# vbus_v2.net
KiCad netlist of a schematic drawn in EAGLE
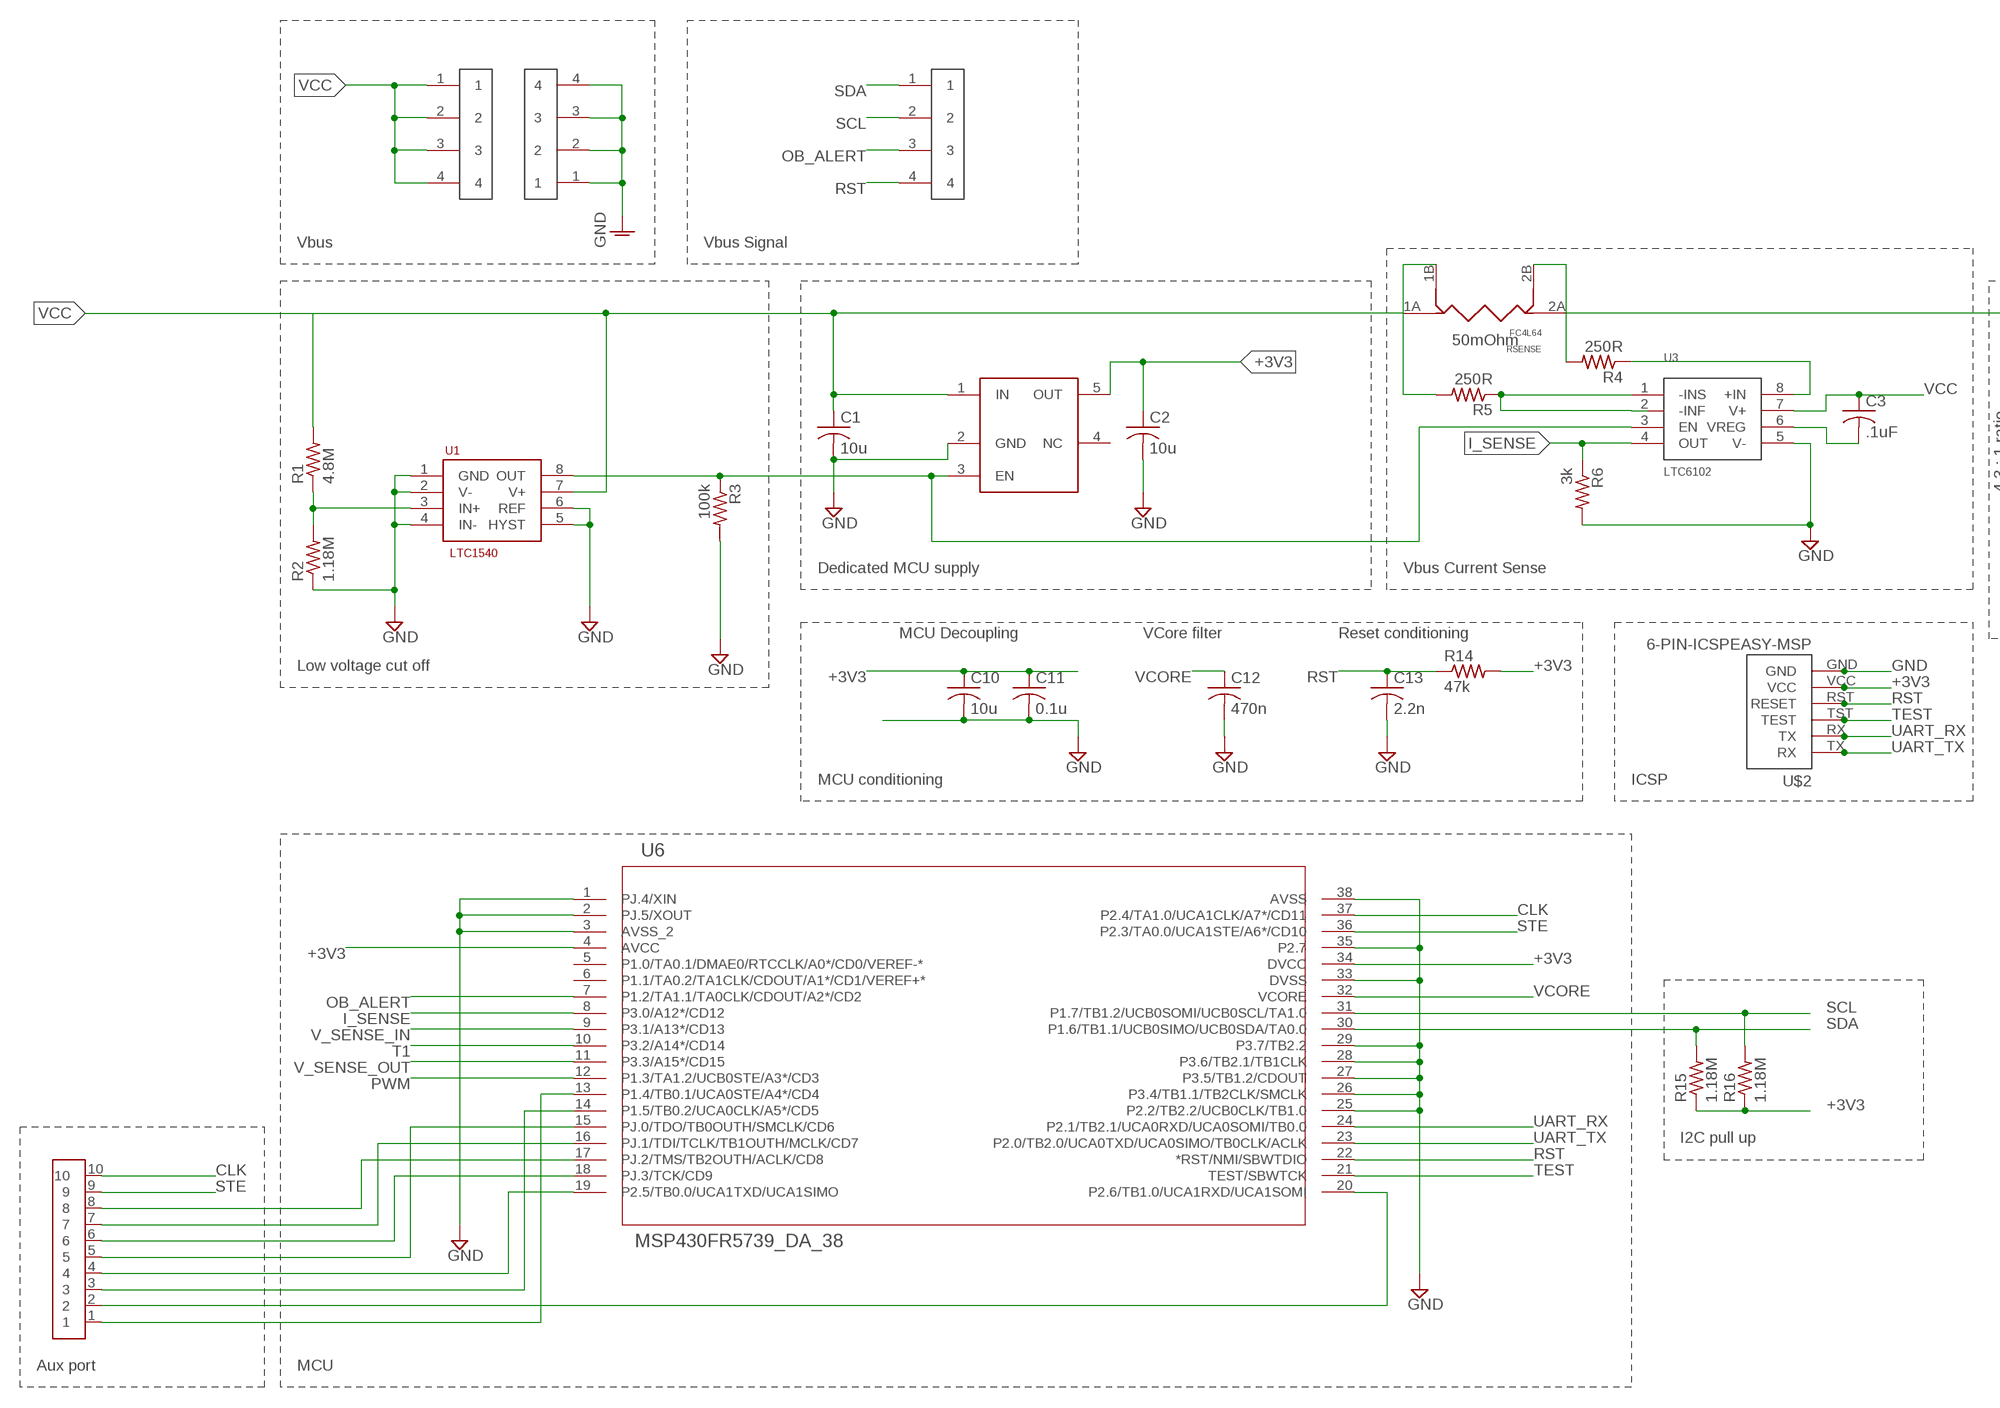
[diagram p0: schematic, sheet 1, part 1 of 2]
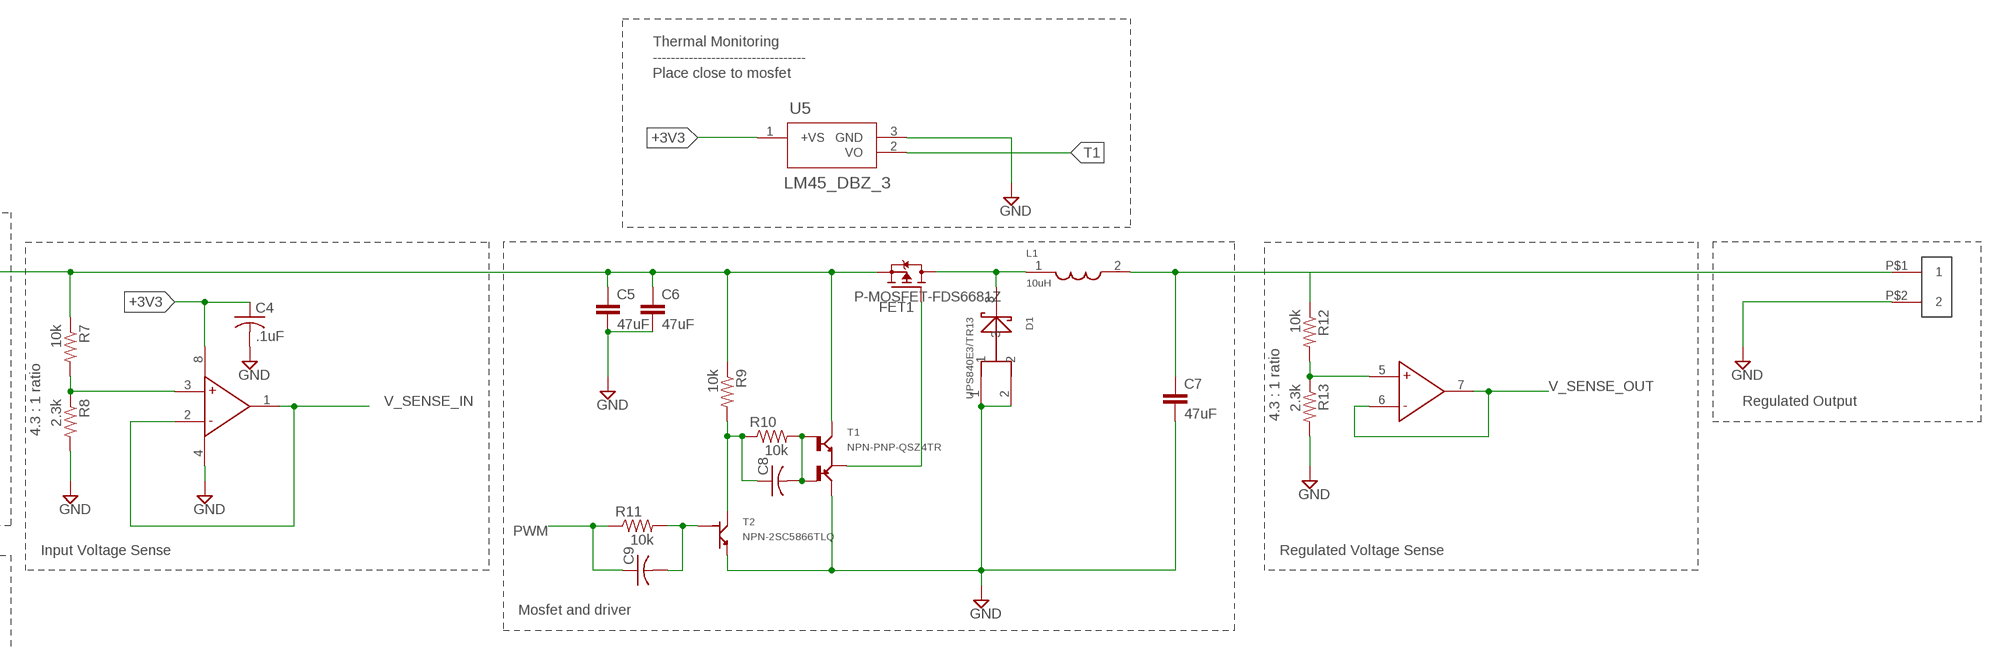
[diagram p1: schematic, sheet 1, part 2 of 2]

(export (version "E")
  (design (tool "Eeschema 10.0.6"))
  (components
    (comp (ref "C1")
      (value "10u")
      (footprint "eagle-import:C1206")
      (libsource (lib "eagle-import") (part "C-USC1206"))
    )
    (comp (ref "C2")
      (value "10u")
      (footprint "eagle-import:C1206")
      (libsource (lib "eagle-import") (part "C-USC1206"))
    )
    (comp (ref "C3")
      (value ".1uF")
      (footprint "eagle-import:C0805")
      (libsource (lib "eagle-import") (part "C-USC0805"))
    )
    (comp (ref "C4")
      (value ".1uF")
      (footprint "eagle-import:C0805")
      (libsource (lib "eagle-import") (part "C-USC0805"))
    )
    (comp (ref "C5")
      (value "47uF")
      (footprint "eagle-import:C1206")
      (libsource (lib "eagle-import") (part "C-EUC1206"))
    )
    (comp (ref "C6")
      (value "47uF")
      (footprint "eagle-import:C1206")
      (libsource (lib "eagle-import") (part "C-EUC1206"))
    )
    (comp (ref "C7")
      (value "47uF")
      (footprint "eagle-import:C1206")
      (libsource (lib "eagle-import") (part "C-EUC1206"))
    )
    (comp (ref "C8")
      (value "C-USC0805")
      (footprint "eagle-import:C0805")
      (libsource (lib "eagle-import") (part "C-USC0805"))
    )
    (comp (ref "C9")
      (value "C-USC0805")
      (footprint "eagle-import:C0805")
      (libsource (lib "eagle-import") (part "C-USC0805"))
    )
    (comp (ref "C10")
      (value "10u")
      (footprint "eagle-import:C1206")
      (libsource (lib "eagle-import") (part "C-USC1206"))
    )
    (comp (ref "C11")
      (value "0.1u")
      (footprint "eagle-import:C1206")
      (libsource (lib "eagle-import") (part "C-USC1206"))
    )
    (comp (ref "C12")
      (value "470n")
      (footprint "eagle-import:C1206")
      (libsource (lib "eagle-import") (part "C-USC1206"))
    )
    (comp (ref "C13")
      (value "2.2n")
      (footprint "eagle-import:C1206")
      (libsource (lib "eagle-import") (part "C-USC1206"))
    )
    (comp (ref "D1")
      (value "UPS840E3/TR13")
      (footprint "eagle-import:UPS840E3")
      (libsource (lib "eagle-import") (part "UPS840E3"))
    )
    (comp (ref "FET1")
      (value "P-MOSFET-FDS6681Z")
      (footprint "eagle-import:SOIC-8")
      (libsource (lib "eagle-import") (part "P-MOSFET-FDS6681Z"))
    )
    (comp (ref "L1")
      (value "10uH")
      (footprint "eagle-import:HCF1007")
      (libsource (lib "eagle-import") (part "HCF1007"))
    )
    (comp (ref "R1")
      (value "4.8M")
      (footprint "eagle-import:R1206")
      (libsource (lib "eagle-import") (part "R-US_R1206"))
    )
    (comp (ref "R2")
      (value "1.18M")
      (footprint "eagle-import:R1206")
      (libsource (lib "eagle-import") (part "R-US_R1206"))
    )
    (comp (ref "R3")
      (value "100k")
      (footprint "eagle-import:R1206")
      (libsource (lib "eagle-import") (part "R-US_R1206"))
    )
    (comp (ref "R4")
      (value "250R")
      (footprint "eagle-import:M0805")
      (libsource (lib "eagle-import") (part "R-US_M0805"))
    )
    (comp (ref "R5")
      (value "250R")
      (footprint "eagle-import:M0805")
      (libsource (lib "eagle-import") (part "R-US_M0805"))
    )
    (comp (ref "R6")
      (value "3k")
      (footprint "eagle-import:M0805")
      (libsource (lib "eagle-import") (part "R-US_M0805"))
    )
    (comp (ref "R7")
      (value "10k")
      (footprint "eagle-import:M0805")
      (libsource (lib "eagle-import") (part "R-US_M0805"))
    )
    (comp (ref "R8")
      (value "2.3k")
      (footprint "eagle-import:M0805")
      (libsource (lib "eagle-import") (part "R-US_M0805"))
    )
    (comp (ref "R9")
      (value "10k")
      (footprint "eagle-import:M0805")
      (libsource (lib "eagle-import") (part "R-US_M0805"))
    )
    (comp (ref "R10")
      (value "10k")
      (footprint "eagle-import:M0805")
      (libsource (lib "eagle-import") (part "R-US_M0805"))
    )
    (comp (ref "R11")
      (value "10k")
      (footprint "eagle-import:M0805")
      (libsource (lib "eagle-import") (part "R-US_M0805"))
    )
    (comp (ref "R12")
      (value "10k")
      (footprint "eagle-import:M0805")
      (libsource (lib "eagle-import") (part "R-US_M0805"))
    )
    (comp (ref "R13")
      (value "2.3k")
      (footprint "eagle-import:M0805")
      (libsource (lib "eagle-import") (part "R-US_M0805"))
    )
    (comp (ref "R14")
      (value "47k")
      (footprint "eagle-import:R1206")
      (libsource (lib "eagle-import") (part "R-US_R1206"))
    )
    (comp (ref "R15")
      (value "1.18M")
      (footprint "eagle-import:R0805")
      (libsource (lib "eagle-import") (part "R-US_R0805"))
    )
    (comp (ref "R16")
      (value "1.18M")
      (footprint "eagle-import:R0805")
      (libsource (lib "eagle-import") (part "R-US_R0805"))
    )
    (comp (ref "RSENSE")
      (value "FC4L64")
      (footprint "eagle-import:FC4L64")
      (libsource (lib "eagle-import") (part "FC4L64"))
    )
    (comp (ref "T1")
      (value "NPN-PNP-QSZ4TR")
      (footprint "eagle-import:TSMT5")
      (libsource (lib "eagle-import") (part "NPN-PNP-QSZ4TR"))
    )
    (comp (ref "T2")
      (value "NPN-2SC5866TLQ")
      (footprint "eagle-import:TSMT3")
      (libsource (lib "eagle-import") (part "NPN-2SC5866TLQ"))
    )
    (comp (ref "U$1")
      (value "MICROPITCH")
      (footprint "eagle-import:2X5-1.27MM")
      (libsource (lib "eagle-import") (part "MICROPITCH"))
    )
    (comp (ref "U$2")
      (value "6-PIN-ICSPEASY-MSP")
      (footprint "eagle-import:EASYMSP-6PIN")
      (libsource (lib "eagle-import") (part "6-PIN-ICSPEASY-MSP"))
    )
    (comp (ref "U$3")
      (value "1X4_HEADER")
      (footprint "eagle-import:1X4-.1HEADER")
      (libsource (lib "eagle-import") (part "1X4_HEADER"))
    )
    (comp (ref "U$5")
      (value "MOLEX-0436500200")
      (footprint "eagle-import:MOLEX_MICROFIT-2")
      (libsource (lib "eagle-import") (part "MOLEX-0436500200"))
    )
    (comp (ref "U$8")
      (value "1X4_HEADER")
      (footprint "eagle-import:1X4-.1HEADER")
      (libsource (lib "eagle-import") (part "1X4_HEADER"))
    )
    (comp (ref "U$11")
      (value "1X4_HEADER")
      (footprint "eagle-import:1X4-.1HEADER")
      (libsource (lib "eagle-import") (part "1X4_HEADER"))
    )
    (comp (ref "U1")
      (value "LTC1540")
      (footprint "eagle-import:S8")
      (libsource (lib "eagle-import") (part "LTC1540"))
    )
    (comp (ref "U2")
      (value "TPS70930-Q1")
      (footprint "eagle-import:SOT-23")
      (libsource (lib "eagle-import") (part "TPS70930-Q1"))
    )
    (comp (ref "U3")
      (value "LTC6102")
      (footprint "eagle-import:MS8")
      (libsource (lib "eagle-import") (part "LTC6102"))
    )
    (comp (ref "U4")
      (value "LMP2202")
      (footprint "eagle-import:D8-L")
      (libsource (lib "eagle-import") (part "LMP2202"))
    )
    (comp (ref "U5")
      (value "LM45_DBZ_3")
      (footprint "eagle-import:MF03A")
      (fields (field (name "PARTNUMBER") "LM45BIM3"))
      (libsource (lib "eagle-import") (part "LM45_DBZ_3"))
    )
    (comp (ref "U6")
      (value "MSP430FR5739_DA_38")
      (footprint "eagle-import:DA38")
      (fields
        (field (name "GENERIC_PART_NUMBER") "MSP430FR5739")
        (field (name "MANUFACTURER") "Texas Instruments")
        (field (name "MANUFACTURER_PART_NUMBER") "msp430fr5739_da_38")
      )
      (libsource (lib "eagle-import") (part "MSP430FR5739_DA_38"))
    )
  )
  (nets
    (net (code "1") (name "+3V3") (class "Default")
      (node (ref "C10") (pin "1") (pinfunction "1_1") (pintype "passive"))
      (node (ref "C11") (pin "1") (pinfunction "1_1") (pintype "passive"))
      (node (ref "C2") (pin "1") (pinfunction "1_1") (pintype "passive"))
      (node (ref "C4") (pin "1") (pinfunction "1_1") (pintype "passive"))
      (node (ref "R14") (pin "2") (pinfunction "2_2") (pintype "passive"))
      (node (ref "R15") (pin "1") (pinfunction "1_1") (pintype "passive"))
      (node (ref "R16") (pin "1") (pinfunction "1_1") (pintype "passive"))
      (node (ref "U$2") (pin "VCC") (pinfunction "VCC_VCC") (pintype "bidirectional"))
      (node (ref "U2") (pin "5") (pinfunction "OUT_5") (pintype "bidirectional"))
      (node (ref "U4") (pin "8") (pinfunction "VIN_8") (pintype "bidirectional"))
      (node (ref "U5") (pin "1") (pinfunction "+VS_1") (pintype "input"))
      (node (ref "U6") (pin "34") (pinfunction "DVCC_34") (pintype "power_in"))
      (node (ref "U6") (pin "4") (pinfunction "AVCC_4") (pintype "power_in"))
    )
    (net (code "2") (name "/CLK") (class "Default")
      (node (ref "U$1") (pin "10") (pinfunction "10_10") (pintype "bidirectional"))
      (node (ref "U6") (pin "37") (pinfunction "P2.4/TA1.0/UCA1CLK/A7*/CD11_37") (pintype "bidirectional"))
    )
    (net (code "3") (name "/OB_ALERT") (class "Default")
      (node (ref "U$8") (pin "3") (pinfunction "3_3") (pintype "bidirectional"))
      (node (ref "U6") (pin "7") (pinfunction "P1.2/TA1.1/TA0CLK/CDOUT/A2*/CD2_7") (pintype "bidirectional"))
    )
    (net (code "4") (name "/PWM") (class "Default")
      (node (ref "C9") (pin "1") (pinfunction "1_1") (pintype "passive"))
      (node (ref "R11") (pin "1") (pinfunction "1_1") (pintype "passive"))
      (node (ref "U6") (pin "12") (pinfunction "P1.3/TA1.2/UCB0STE/A3*/CD3_12") (pintype "bidirectional"))
    )
    (net (code "5") (name "/RST") (class "Default")
      (node (ref "C13") (pin "1") (pinfunction "1_1") (pintype "passive"))
      (node (ref "R14") (pin "1") (pinfunction "1_1") (pintype "passive"))
      (node (ref "U$2") (pin "RST") (pinfunction "RESET_RST") (pintype "bidirectional"))
      (node (ref "U$8") (pin "4") (pinfunction "4_4") (pintype "bidirectional"))
      (node (ref "U6") (pin "22") (pinfunction "*RST/NMI/SBWTDIO_22") (pintype "bidirectional"))
    )
    (net (code "6") (name "/SCL") (class "Default")
      (node (ref "R16") (pin "2") (pinfunction "2_2") (pintype "passive"))
      (node (ref "U$8") (pin "2") (pinfunction "2_2") (pintype "bidirectional"))
      (node (ref "U6") (pin "31") (pinfunction "P1.7/TB1.2/UCB0SOMI/UCB0SCL/TA1.0_31") (pintype "bidirectional"))
    )
    (net (code "7") (name "/SDA") (class "Default")
      (node (ref "R15") (pin "2") (pinfunction "2_2") (pintype "passive"))
      (node (ref "U$8") (pin "1") (pinfunction "1_1") (pintype "bidirectional"))
      (node (ref "U6") (pin "30") (pinfunction "P1.6/TB1.1/UCB0SIMO/UCB0SDA/TA0.0_30") (pintype "bidirectional"))
    )
    (net (code "8") (name "/STE") (class "Default")
      (node (ref "U$1") (pin "9") (pinfunction "9_9") (pintype "bidirectional"))
      (node (ref "U6") (pin "36") (pinfunction "P2.3/TA0.0/UCA1STE/A6*/CD10_36") (pintype "bidirectional"))
    )
    (net (code "9") (name "/TEST") (class "Default")
      (node (ref "U$2") (pin "TST") (pinfunction "TEST_TST") (pintype "bidirectional"))
      (node (ref "U6") (pin "21") (pinfunction "TEST/SBWTCK_21") (pintype "bidirectional"))
    )
    (net (code "10") (name "/UART_RX") (class "Default")
      (node (ref "U$2") (pin "RX") (pinfunction "TX_RX") (pintype "bidirectional"))
      (node (ref "U6") (pin "24") (pinfunction "P2.1/TB2.1/UCA0RXD/UCA0SOMI/TB0.0_24") (pintype "bidirectional"))
    )
    (net (code "11") (name "/UART_TX") (class "Default")
      (node (ref "U$2") (pin "TX") (pinfunction "RX_TX") (pintype "bidirectional"))
      (node (ref "U6") (pin "23") (pinfunction "P2.0/TB2.0/UCA0TXD/UCA0SIMO/TB0CLK/ACLK_23") (pintype "bidirectional"))
    )
    (net (code "12") (name "/VCORE") (class "Default")
      (node (ref "C12") (pin "1") (pinfunction "1_1") (pintype "passive"))
      (node (ref "U6") (pin "32") (pinfunction "VCORE_32") (pintype "power_in"))
    )
    (net (code "13") (name "/V_SENSE_IN") (class "Default")
      (node (ref "U4") (pin "1") (pinfunction "OUT_1") (pintype "bidirectional"))
      (node (ref "U4") (pin "2") (pinfunction "-_2") (pintype "bidirectional"))
      (node (ref "U6") (pin "9") (pinfunction "P3.1/A13*/CD13_9") (pintype "bidirectional"))
    )
    (net (code "14") (name "/V_SENSE_OUT") (class "Default")
      (node (ref "U4") (pin "6") (pinfunction "-_6") (pintype "bidirectional"))
      (node (ref "U4") (pin "7") (pinfunction "OUT_7") (pintype "bidirectional"))
      (node (ref "U6") (pin "11") (pinfunction "P3.3/A15*/CD15_11") (pintype "bidirectional"))
    )
    (net (code "15") (name "GND") (class "Default")
      (node (ref "C1") (pin "2") (pinfunction "2_2") (pintype "passive"))
      (node (ref "C10") (pin "2") (pinfunction "2_2") (pintype "passive"))
      (node (ref "C11") (pin "2") (pinfunction "2_2") (pintype "passive"))
      (node (ref "C12") (pin "2") (pinfunction "2_2") (pintype "passive"))
      (node (ref "C13") (pin "2") (pinfunction "2_2") (pintype "passive"))
      (node (ref "C2") (pin "2") (pinfunction "2_2") (pintype "passive"))
      (node (ref "C4") (pin "2") (pinfunction "2_2") (pintype "passive"))
      (node (ref "C5") (pin "2") (pinfunction "2_2") (pintype "passive"))
      (node (ref "C6") (pin "2") (pinfunction "2_2") (pintype "passive"))
      (node (ref "C7") (pin "2") (pinfunction "2_2") (pintype "passive"))
      (node (ref "D1") (pin "1") (pinfunction "1_1") (pintype "bidirectional"))
      (node (ref "D1") (pin "2") (pinfunction "2_2") (pintype "bidirectional"))
      (node (ref "R13") (pin "2") (pinfunction "2_2") (pintype "passive"))
      (node (ref "R2") (pin "1") (pinfunction "1_1") (pintype "passive"))
      (node (ref "R3") (pin "2") (pinfunction "2_2") (pintype "passive"))
      (node (ref "R6") (pin "2") (pinfunction "2_2") (pintype "passive"))
      (node (ref "R8") (pin "2") (pinfunction "2_2") (pintype "passive"))
      (node (ref "T1") (pin "5") (pinfunction "E_5") (pintype "bidirectional"))
      (node (ref "T2") (pin "2") (pinfunction "E_2") (pintype "bidirectional"))
      (node (ref "U$2") (pin "GND") (pinfunction "GND_GND") (pintype "bidirectional"))
      (node (ref "U$3") (pin "1") (pinfunction "1_1") (pintype "bidirectional"))
      (node (ref "U$3") (pin "2") (pinfunction "2_2") (pintype "bidirectional"))
      (node (ref "U$3") (pin "3") (pinfunction "3_3") (pintype "bidirectional"))
      (node (ref "U$3") (pin "4") (pinfunction "4_4") (pintype "bidirectional"))
      (node (ref "U$5") (pin "P$2") (pinfunction "2_P$2") (pintype "bidirectional"))
      (node (ref "U1") (pin "1") (pinfunction "GND_1") (pintype "bidirectional"))
      (node (ref "U1") (pin "2") (pinfunction "V-_2") (pintype "bidirectional"))
      (node (ref "U1") (pin "4") (pinfunction "IN-_4") (pintype "bidirectional"))
      (node (ref "U1") (pin "5") (pinfunction "HYST_5") (pintype "bidirectional"))
      (node (ref "U1") (pin "6") (pinfunction "REF_6") (pintype "bidirectional"))
      (node (ref "U2") (pin "2") (pinfunction "GND_2") (pintype "bidirectional"))
      (node (ref "U3") (pin "5") (pinfunction "V-_5") (pintype "power_in"))
      (node (ref "U4") (pin "4") (pinfunction "GND_4") (pintype "bidirectional"))
      (node (ref "U5") (pin "3") (pinfunction "GND_3") (pintype "passive"))
      (node (ref "U6") (pin "1") (pinfunction "PJ.4/XIN_1") (pintype "bidirectional"))
      (node (ref "U6") (pin "2") (pinfunction "PJ.5/XOUT_2") (pintype "bidirectional"))
      (node (ref "U6") (pin "25") (pinfunction "P2.2/TB2.2/UCB0CLK/TB1.0_25") (pintype "bidirectional"))
      (node (ref "U6") (pin "26") (pinfunction "P3.4/TB1.1/TB2CLK/SMCLK_26") (pintype "bidirectional"))
      (node (ref "U6") (pin "27") (pinfunction "P3.5/TB1.2/CDOUT_27") (pintype "bidirectional"))
      (node (ref "U6") (pin "28") (pinfunction "P3.6/TB2.1/TB1CLK_28") (pintype "bidirectional"))
      (node (ref "U6") (pin "29") (pinfunction "P3.7/TB2.2_29") (pintype "bidirectional"))
      (node (ref "U6") (pin "3") (pinfunction "AVSS_2_3") (pintype "power_in"))
      (node (ref "U6") (pin "33") (pinfunction "DVSS_33") (pintype "power_in"))
      (node (ref "U6") (pin "35") (pinfunction "P2.7_35") (pintype "bidirectional"))
      (node (ref "U6") (pin "38") (pinfunction "AVSS_38") (pintype "power_in"))
    )
    (net (code "16") (name "I_SENSE") (class "Default")
      (node (ref "R6") (pin "1") (pinfunction "1_1") (pintype "passive"))
      (node (ref "U3") (pin "4") (pinfunction "OUT_4") (pintype "power_in"))
      (node (ref "U6") (pin "8") (pinfunction "P3.0/A12*/CD12_8") (pintype "bidirectional"))
    )
    (net (code "17") (name "Net-(FET1-G)") (class "Default")
      (node (ref "FET1") (pin "4") (pinfunction "G_4") (pintype "passive"))
      (node (ref "T1") (pin "2") (pinfunction "G_2") (pintype "bidirectional"))
    )
    (net (code "18") (name "Net-(L1-A)") (class "Default")
      (node (ref "D1") (pin "3") (pinfunction "3_3") (pintype "bidirectional"))
      (node (ref "FET1") (pin "1") (pinfunction "S_1") (pintype "passive"))
      (node (ref "FET1") (pin "2") (pinfunction "S_2") (pintype "passive"))
      (node (ref "FET1") (pin "3") (pinfunction "S_3") (pintype "passive"))
      (node (ref "L1") (pin "1") (pinfunction "A_1") (pintype "bidirectional"))
    )
    (net (code "19") (name "Net-(L1-B)") (class "Default")
      (node (ref "C7") (pin "1") (pinfunction "1_1") (pintype "passive"))
      (node (ref "L1") (pin "2") (pinfunction "B_2") (pintype "bidirectional"))
      (node (ref "R12") (pin "1") (pinfunction "1_1") (pintype "passive"))
      (node (ref "U$5") (pin "P$1") (pinfunction "1_P$1") (pintype "bidirectional"))
    )
    (net (code "20") (name "Net-(RSENSE-1A)") (class "Default")
      (node (ref "C5") (pin "1") (pinfunction "1_1") (pintype "passive"))
      (node (ref "C6") (pin "1") (pinfunction "1_1") (pintype "passive"))
      (node (ref "FET1") (pin "5") (pinfunction "D_5") (pintype "passive"))
      (node (ref "FET1") (pin "6") (pinfunction "D_6") (pintype "passive"))
      (node (ref "FET1") (pin "7") (pinfunction "D_7") (pintype "passive"))
      (node (ref "FET1") (pin "8") (pinfunction "D_8") (pintype "passive"))
      (node (ref "R7") (pin "1") (pinfunction "1_1") (pintype "passive"))
      (node (ref "R9") (pin "1") (pinfunction "1_1") (pintype "passive"))
      (node (ref "RSENSE") (pin "2A") (pinfunction "1A_2A") (pintype "bidirectional"))
      (node (ref "T1") (pin "4") (pinfunction "C_4") (pintype "bidirectional"))
    )
    (net (code "21") (name "Net-(RSENSE-1B)") (class "Default")
      (node (ref "R4") (pin "2") (pinfunction "2_2") (pintype "passive"))
      (node (ref "RSENSE") (pin "2B") (pinfunction "1B_2B") (pintype "bidirectional"))
    )
    (net (code "22") (name "Net-(RSENSE-2B)") (class "Default")
      (node (ref "R5") (pin "2") (pinfunction "2_2") (pintype "passive"))
      (node (ref "RSENSE") (pin "1B") (pinfunction "2B_1B") (pintype "bidirectional"))
    )
    (net (code "23") (name "Net-(T1-G1)") (class "Default")
      (node (ref "C8") (pin "2") (pinfunction "2_2") (pintype "passive"))
      (node (ref "R10") (pin "2") (pinfunction "2_2") (pintype "passive"))
      (node (ref "T1") (pin "1") (pinfunction "G2_1") (pintype "bidirectional"))
      (node (ref "T1") (pin "3") (pinfunction "G1_3") (pintype "bidirectional"))
    )
    (net (code "24") (name "Net-(T2-B)") (class "Default")
      (node (ref "C9") (pin "2") (pinfunction "2_2") (pintype "passive"))
      (node (ref "R11") (pin "2") (pinfunction "2_2") (pintype "passive"))
      (node (ref "T2") (pin "1") (pinfunction "B_1") (pintype "bidirectional"))
    )
    (net (code "25") (name "Net-(T2-C)") (class "Default")
      (node (ref "C8") (pin "1") (pinfunction "1_1") (pintype "passive"))
      (node (ref "R10") (pin "1") (pinfunction "1_1") (pintype "passive"))
      (node (ref "R9") (pin "2") (pinfunction "2_2") (pintype "passive"))
      (node (ref "T2") (pin "3") (pinfunction "C_3") (pintype "bidirectional"))
    )
    (net (code "26") (name "Net-(U1-IN+)") (class "Default")
      (node (ref "R1") (pin "1") (pinfunction "1_1") (pintype "passive"))
      (node (ref "R2") (pin "2") (pinfunction "2_2") (pintype "passive"))
      (node (ref "U1") (pin "3") (pinfunction "IN+_3") (pintype "bidirectional"))
    )
    (net (code "27") (name "Net-(U1-OUT)") (class "Default")
      (node (ref "R3") (pin "1") (pinfunction "1_1") (pintype "passive"))
      (node (ref "U1") (pin "8") (pinfunction "OUT_8") (pintype "bidirectional"))
      (node (ref "U2") (pin "3") (pinfunction "EN_3") (pintype "bidirectional"))
      (node (ref "U3") (pin "3") (pinfunction "EN_3") (pintype "power_in"))
    )
    (net (code "28") (name "Net-(U3-+IN)") (class "Default")
      (node (ref "R4") (pin "1") (pinfunction "1_1") (pintype "passive"))
      (node (ref "U3") (pin "8") (pinfunction "+IN_8") (pintype "power_in"))
    )
    (net (code "29") (name "Net-(U3--INF)") (class "Default")
      (node (ref "R5") (pin "1") (pinfunction "1_1") (pintype "passive"))
      (node (ref "U3") (pin "1") (pinfunction "-INS_1") (pintype "power_in"))
      (node (ref "U3") (pin "2") (pinfunction "-INF_2") (pintype "power_in"))
    )
    (net (code "30") (name "Net-(U3-VREG)") (class "Default")
      (node (ref "C3") (pin "2") (pinfunction "2_2") (pintype "passive"))
      (node (ref "U3") (pin "6") (pinfunction "VREG_6") (pintype "power_in"))
    )
    (net (code "31") (name "Net-(U4A-+)") (class "Default")
      (node (ref "R7") (pin "2") (pinfunction "2_2") (pintype "passive"))
      (node (ref "R8") (pin "1") (pinfunction "1_1") (pintype "passive"))
      (node (ref "U4") (pin "3") (pinfunction "+_3") (pintype "bidirectional"))
    )
    (net (code "32") (name "Net-(U4B-+)") (class "Default")
      (node (ref "R12") (pin "2") (pinfunction "2_2") (pintype "passive"))
      (node (ref "R13") (pin "1") (pinfunction "1_1") (pintype "passive"))
      (node (ref "U4") (pin "5") (pinfunction "+_5") (pintype "bidirectional"))
    )
    (net (code "33") (name "Net-(U6-P1.4{slash}TB0.1{slash}UCA0STE{slash}A4*{slash}CD4)") (class "Default")
      (node (ref "U$1") (pin "1") (pinfunction "1_1") (pintype "bidirectional"))
      (node (ref "U6") (pin "13") (pinfunction "P1.4/TB0.1/UCA0STE/A4*/CD4_13") (pintype "bidirectional"))
    )
    (net (code "34") (name "Net-(U6-P1.5{slash}TB0.2{slash}UCA0CLK{slash}A5*{slash}CD5)") (class "Default")
      (node (ref "U$1") (pin "3") (pinfunction "3_3") (pintype "bidirectional"))
      (node (ref "U6") (pin "14") (pinfunction "P1.5/TB0.2/UCA0CLK/A5*/CD5_14") (pintype "bidirectional"))
    )
    (net (code "35") (name "Net-(U6-P2.5{slash}TB0.0{slash}UCA1TXD{slash}UCA1SIMO)") (class "Default")
      (node (ref "U$1") (pin "4") (pinfunction "4_4") (pintype "bidirectional"))
      (node (ref "U6") (pin "19") (pinfunction "P2.5/TB0.0/UCA1TXD/UCA1SIMO_19") (pintype "bidirectional"))
    )
    (net (code "36") (name "Net-(U6-P2.6{slash}TB1.0{slash}UCA1RXD{slash}UCA1SOMI)") (class "Default")
      (node (ref "U$1") (pin "2") (pinfunction "2_2") (pintype "bidirectional"))
      (node (ref "U6") (pin "20") (pinfunction "P2.6/TB1.0/UCA1RXD/UCA1SOMI_20") (pintype "bidirectional"))
    )
    (net (code "37") (name "Net-(U6-PJ.0{slash}TDO{slash}TB0OUTH{slash}SMCLK{slash}CD6)") (class "Default")
      (node (ref "U$1") (pin "5") (pinfunction "5_5") (pintype "bidirectional"))
      (node (ref "U6") (pin "15") (pinfunction "PJ.0/TDO/TB0OUTH/SMCLK/CD6_15") (pintype "bidirectional"))
    )
    (net (code "38") (name "Net-(U6-PJ.1{slash}TDI{slash}TCLK{slash}TB1OUTH{slash}MCLK{slash}CD7)") (class "Default")
      (node (ref "U$1") (pin "7") (pinfunction "7_7") (pintype "bidirectional"))
      (node (ref "U6") (pin "16") (pinfunction "PJ.1/TDI/TCLK/TB1OUTH/MCLK/CD7_16") (pintype "bidirectional"))
    )
    (net (code "39") (name "Net-(U6-PJ.2{slash}TMS{slash}TB2OUTH{slash}ACLK{slash}CD8)") (class "Default")
      (node (ref "U$1") (pin "8") (pinfunction "8_8") (pintype "bidirectional"))
      (node (ref "U6") (pin "17") (pinfunction "PJ.2/TMS/TB2OUTH/ACLK/CD8_17") (pintype "bidirectional"))
    )
    (net (code "40") (name "Net-(U6-PJ.3{slash}TCK{slash}CD9)") (class "Default")
      (node (ref "U$1") (pin "6") (pinfunction "6_6") (pintype "bidirectional"))
      (node (ref "U6") (pin "18") (pinfunction "PJ.3/TCK/CD9_18") (pintype "bidirectional"))
    )
    (net (code "41") (name "T1") (class "Default")
      (node (ref "U5") (pin "2") (pinfunction "VO_2") (pintype "output"))
      (node (ref "U6") (pin "10") (pinfunction "P3.2/A14*/CD14_10") (pintype "bidirectional"))
    )
    (net (code "42") (name "VCC") (class "Default")
      (node (ref "C1") (pin "1") (pinfunction "1_1") (pintype "passive"))
      (node (ref "C3") (pin "1") (pinfunction "1_1") (pintype "passive"))
      (node (ref "R1") (pin "2") (pinfunction "2_2") (pintype "passive"))
      (node (ref "RSENSE") (pin "1A") (pinfunction "2A_1A") (pintype "bidirectional"))
      (node (ref "U$11") (pin "1") (pinfunction "1_1") (pintype "bidirectional"))
      (node (ref "U$11") (pin "2") (pinfunction "2_2") (pintype "bidirectional"))
      (node (ref "U$11") (pin "3") (pinfunction "3_3") (pintype "bidirectional"))
      (node (ref "U$11") (pin "4") (pinfunction "4_4") (pintype "bidirectional"))
      (node (ref "U1") (pin "7") (pinfunction "V+_7") (pintype "bidirectional"))
      (node (ref "U2") (pin "1") (pinfunction "IN_1") (pintype "bidirectional"))
      (node (ref "U3") (pin "7") (pinfunction "V+_7") (pintype "power_in"))
    )
    (net (code "43") (name "unconnected-(U2-NC-Pad4)") (class "Default")
      (node (ref "U2") (pin "4") (pinfunction "NC_4") (pintype "bidirectional"))
    )
    (net (code "44") (name "unconnected-(U6-P1.0{slash}TA0.1{slash}DMAE0{slash}RTCCLK{slash}A0*{slash}CD0{slash}VEREF-*-Pad5)") (class "Default")
      (node (ref "U6") (pin "5") (pinfunction "P1.0/TA0.1/DMAE0/RTCCLK/A0*/CD0/VEREF-*_5") (pintype "bidirectional"))
    )
    (net (code "45") (name "unconnected-(U6-P1.1{slash}TA0.2{slash}TA1CLK{slash}CDOUT{slash}A1*{slash}CD1{slash}VEREF+*-Pad6)") (class "Default")
      (node (ref "U6") (pin "6") (pinfunction "P1.1/TA0.2/TA1CLK/CDOUT/A1*/CD1/VEREF+*_6") (pintype "bidirectional"))
    )
  )
)
